# Alimentacion.net
KiCad netlist of a schematic drawn in Altium Designer
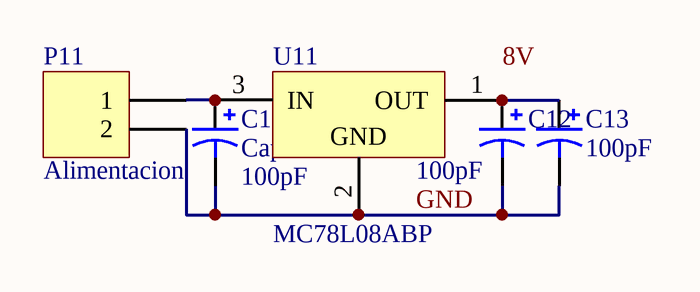
[diagram p0: Alimentacion.SchDoc]

(export (version "E")
  (design (tool "Eeschema 10.0.6"))
  (components
    (comp (ref "C11")
      (value "Cap Pol3")
      (footprint "C0805")
      (description "Polarized Capacitor (Surface Mount)")
      (fields (field (name "ALTIUM_VALUE") "100pF") (field (name "PUBLISHER") "Altium Limited"))
      (libsource (lib "Miscellaneous Devices") (part "Cap Pol3"))
    )
    (comp (ref "C12")
      (value "100pF")
      (footprint "C0805")
      (description "Polarized Capacitor (Surface Mount)")
      (fields (field (name "Comment") "Cap Pol3") (field (name "PUBLISHER") "Altium Limited"))
      (libsource (lib "Miscellaneous Devices") (part "Cap Pol3"))
    )
    (comp (ref "C13")
      (value "100pF")
      (footprint "C0805")
      (description "Polarized Capacitor (Surface Mount)")
      (fields (field (name "Comment") "Cap Pol3") (field (name "PUBLISHER") "Altium Limited"))
      (libsource (lib "Miscellaneous Devices") (part "Cap Pol3"))
    )
    (comp (ref "P11")
      (value "Alimentacion")
      (footprint "HDR1X2")
      (description "Header, 2-Pin")
      (fields (field (name "PUBLISHER") "Altium Limited"))
      (libsource (lib "Miscellaneous Connectors") (part "Header 2"))
    )
    (comp (ref "U11")
      (value "MC78L08ABP")
      (footprint "29-04")
      (description "3-Terminal Low-Current Positive Fixed Voltage Regulator")
      (fields (field (name "PUBLISHER") "Altium Limited"))
      (libsource (lib "Motorola Power Mgt Voltage Regulator") (part "MC78L08ABP"))
    )
  )
  (nets
    (net (code "2") (name "/GND") (class "Default")
      (node (ref "C11") (pin "2") (pinfunction "2_2") (pintype "passive"))
      (node (ref "C12") (pin "2") (pinfunction "2_2") (pintype "passive"))
      (node (ref "C13") (pin "2") (pinfunction "2_2") (pintype "passive"))
      (node (ref "P11") (pin "2") (pinfunction "2_2") (pintype "passive"))
      (node (ref "U11") (pin "2") (pinfunction "GND_2") (pintype "power_in"))
    )
    (net (code "3") (name "Net-(U11-IN)") (class "Default")
      (node (ref "C11") (pin "1") (pinfunction "1_1") (pintype "passive"))
      (node (ref "P11") (pin "1") (pinfunction "1_1") (pintype "passive"))
      (node (ref "U11") (pin "3") (pinfunction "IN_3") (pintype "power_in"))
    )
    (net (code "4") (name "Net-(U11-OUT)") (class "Default")
      (node (ref "C12") (pin "1") (pinfunction "1_1") (pintype "passive"))
      (node (ref "C13") (pin "1") (pinfunction "1_1") (pintype "passive"))
      (node (ref "U11") (pin "1") (pinfunction "OUT_1") (pintype "power_in"))
    )
  )
)
